# RTI-Dome-eth-ESP32.net
KiCad netlist of a schematic drawn in EAGLE
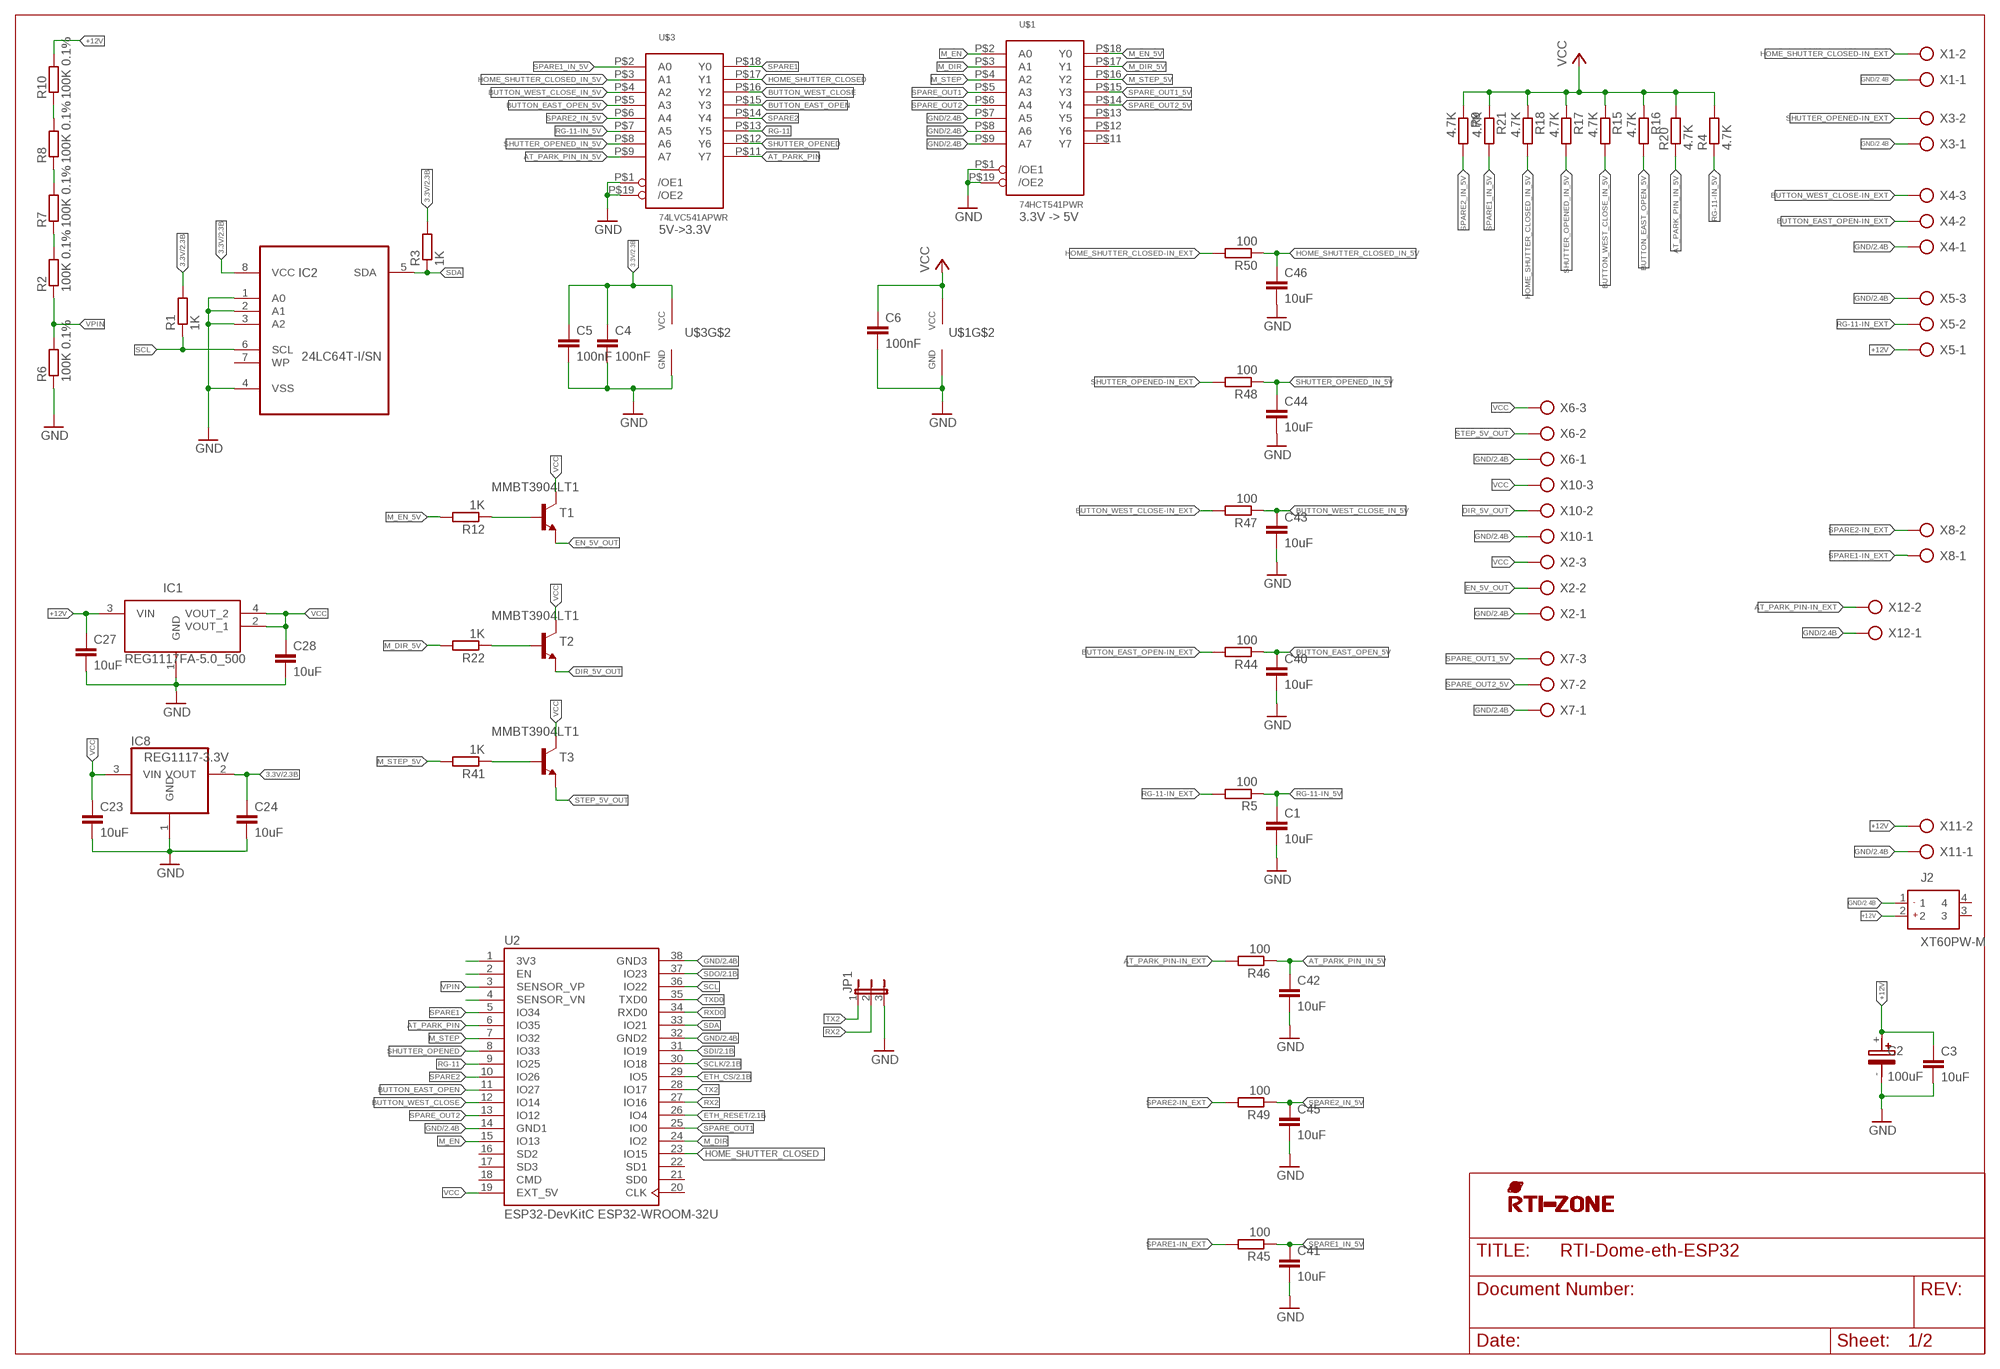
[diagram p0: schematic, sheet 1]
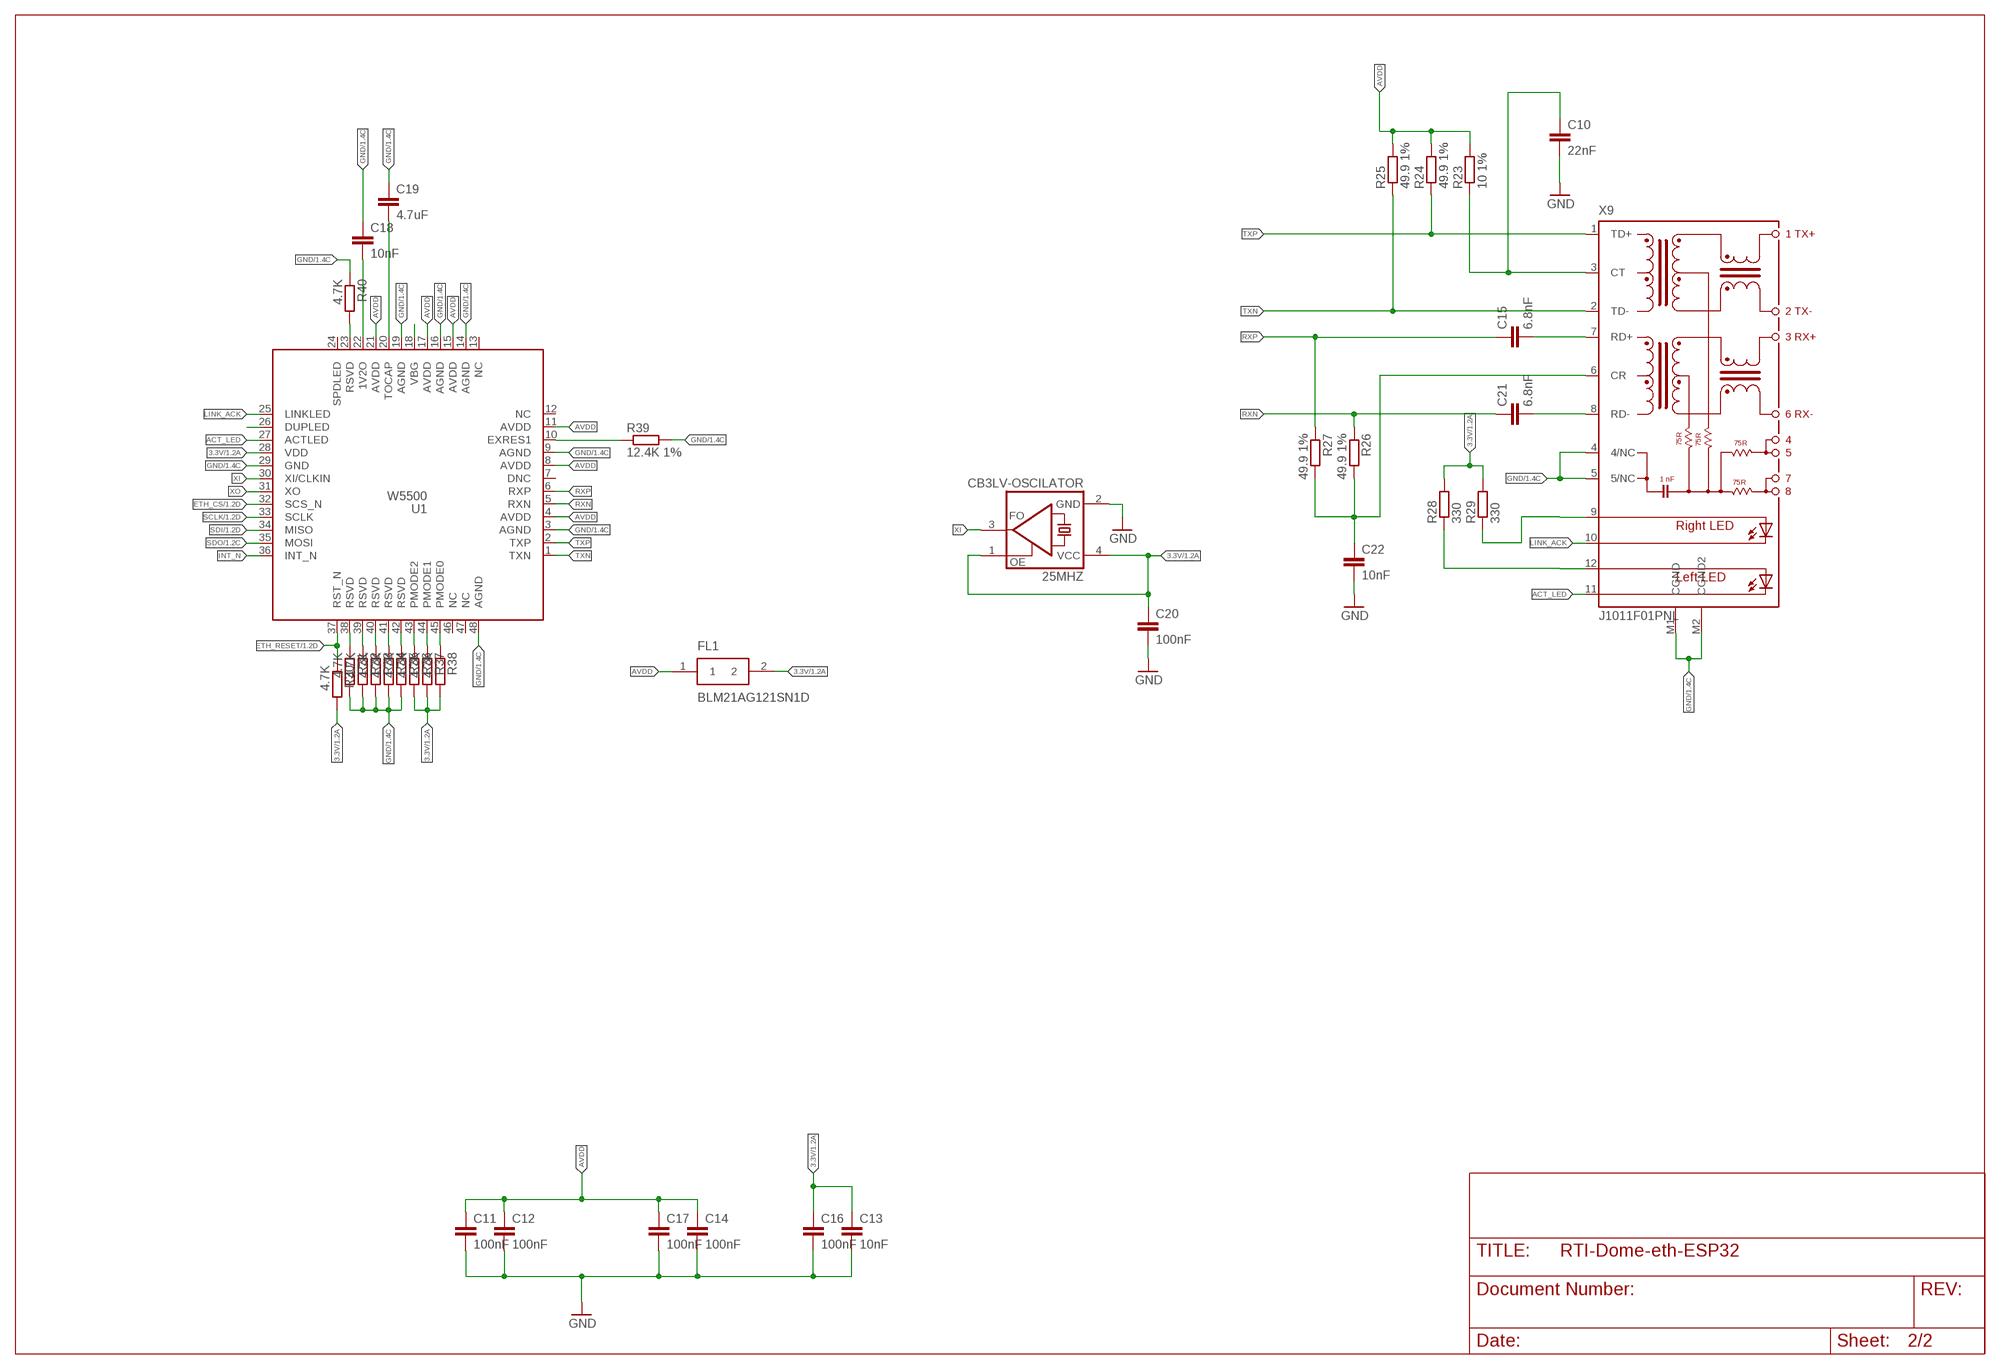
[diagram p1: schematic, sheet 2]

(export (version "E")
  (design (tool "Eeschema 10.0.6"))
  (components
    (comp (ref "C1")
      (value "10uF")
      (footprint "eagle-import:C0603")
      (fields (field (name "MPN") "CC0805KKX5R8BB106"))
      (libsource (lib "eagle-import") (part "C-EUC0603"))
    )
    (comp (ref "C2")
      (value "100uF")
      (footprint "eagle-import:UD-10X10_NICHICON")
      (fields (field (name "MPN") "MAL215099804E3"))
      (libsource (lib "eagle-import") (part "MAL215099804E3{dblquote}{dblquote}"))
    )
    (comp (ref "C3")
      (value "10uF")
      (footprint "eagle-import:C0603")
      (fields (field (name "MPN") "CC0805KKX5R8BB106"))
      (libsource (lib "eagle-import") (part "C-EUC0603"))
    )
    (comp (ref "C4")
      (value "100nF")
      (footprint "eagle-import:C0603")
      (fields (field (name "MPN") "0805YD104KAT2A"))
      (libsource (lib "eagle-import") (part "C-EUC0603"))
    )
    (comp (ref "C5")
      (value "100nF")
      (footprint "eagle-import:C0603")
      (fields (field (name "MPN") "0805YD104KAT2A"))
      (libsource (lib "eagle-import") (part "C-EUC0603"))
    )
    (comp (ref "C6")
      (value "100nF")
      (footprint "eagle-import:C0603")
      (fields (field (name "MPN") "0805YD104KAT2A"))
      (libsource (lib "eagle-import") (part "C-EUC0603"))
    )
    (comp (ref "C23")
      (value "10uF")
      (footprint "eagle-import:C0603")
      (fields (field (name "MPN") "CC0805KKX5R8BB106"))
      (libsource (lib "eagle-import") (part "C-EUC0603"))
    )
    (comp (ref "C24")
      (value "10uF")
      (footprint "eagle-import:C0603")
      (fields (field (name "MPN") "CC0805KKX5R8BB106"))
      (libsource (lib "eagle-import") (part "C-EUC0603"))
    )
    (comp (ref "C27")
      (value "10uF")
      (footprint "eagle-import:C0603")
      (fields (field (name "MPN") "CC0805KKX5R8BB106"))
      (libsource (lib "eagle-import") (part "C-EUC0603"))
    )
    (comp (ref "C28")
      (value "10uF")
      (footprint "eagle-import:C0603")
      (fields (field (name "MPN") "CC0805KKX5R8BB106"))
      (libsource (lib "eagle-import") (part "C-EUC0603"))
    )
    (comp (ref "C40")
      (value "10uF")
      (footprint "eagle-import:C0603")
      (fields (field (name "MPN") "CC0805KKX5R8BB106"))
      (libsource (lib "eagle-import") (part "C-EUC0603"))
    )
    (comp (ref "C41")
      (value "10uF")
      (footprint "eagle-import:C0603")
      (fields (field (name "MPN") "CC0805KKX5R8BB106"))
      (libsource (lib "eagle-import") (part "C-EUC0603"))
    )
    (comp (ref "C42")
      (value "10uF")
      (footprint "eagle-import:C0603")
      (fields (field (name "MPN") "CC0805KKX5R8BB106"))
      (libsource (lib "eagle-import") (part "C-EUC0603"))
    )
    (comp (ref "C43")
      (value "10uF")
      (footprint "eagle-import:C0603")
      (fields (field (name "MPN") "CC0805KKX5R8BB106"))
      (libsource (lib "eagle-import") (part "C-EUC0603"))
    )
    (comp (ref "C44")
      (value "10uF")
      (footprint "eagle-import:C0603")
      (fields (field (name "MPN") "CC0805KKX5R8BB106"))
      (libsource (lib "eagle-import") (part "C-EUC0603"))
    )
    (comp (ref "C45")
      (value "10uF")
      (footprint "eagle-import:C0603")
      (fields (field (name "MPN") "CC0805KKX5R8BB106"))
      (libsource (lib "eagle-import") (part "C-EUC0603"))
    )
    (comp (ref "C46")
      (value "10uF")
      (footprint "eagle-import:C0603")
      (fields (field (name "MPN") "CC0805KKX5R8BB106"))
      (libsource (lib "eagle-import") (part "C-EUC0603"))
    )
    (comp (ref "IC1")
      (value "REG1117FA-5.0_500")
      (footprint "eagle-import:REG1117FA50500")
      (fields
        (field (name "ARROW_PART_NUMBER") "REG1117FA-5.0/500")
        (field (name "MOUSER_PART_NUMBER") "595-REG1117FA50/500")
      )
      (libsource (lib "eagle-import") (part "REG1117FA-5.0_500"))
    )
    (comp (ref "IC2")
      (value "24LC64T-I/SN")
      (footprint "eagle-import:SOIC127P600X175-8N")
      (libsource (lib "eagle-import") (part "24LC64T-I/SN"))
    )
    (comp (ref "IC8")
      (value "REG1117-3.3V")
      (footprint "eagle-import:SOT223")
      (fields (field (name "MPN") "REG1117") (field (name "MPN_1") "REG1117-3.3/2K5"))
      (libsource (lib "eagle-import") (part "REG1117"))
    )
    (comp (ref "J2")
      (value "XT60PW-M")
      (footprint "eagle-import:XT60PWM")
      (libsource (lib "eagle-import") (part "XT60PW-M"))
    )
    (comp (ref "JP1")
      (value "JP2E")
      (footprint "eagle-import:JP2")
      (libsource (lib "eagle-import") (part "JP2E"))
    )
    (comp (ref "R1")
      (value "1K")
      (footprint "eagle-import:R0603")
      (fields (field (name "MPN") "RT0805FRE071KL"))
      (libsource (lib "eagle-import") (part "R-EU_R0603"))
    )
    (comp (ref "R2")
      (value "100K 0.1%")
      (footprint "eagle-import:R0603")
      (fields (field (name "MPN") "AT0805BRD07100KL"))
      (libsource (lib "eagle-import") (part "R-EU_R0603"))
    )
    (comp (ref "R3")
      (value "1K")
      (footprint "eagle-import:R0603")
      (fields (field (name "MPN") "RT0805FRE071KL"))
      (libsource (lib "eagle-import") (part "R-EU_R0603"))
    )
    (comp (ref "R4")
      (value "4.7K")
      (footprint "eagle-import:R0603")
      (fields (field (name "MPN") "RT0805FRE074K7L"))
      (libsource (lib "eagle-import") (part "R-EU_R0603"))
    )
    (comp (ref "R5")
      (value "100")
      (footprint "eagle-import:R0603")
      (fields (field (name "MPN") "RT0805FRD07100RL"))
      (libsource (lib "eagle-import") (part "R-EU_R0603"))
    )
    (comp (ref "R6")
      (value "100K 0.1%")
      (footprint "eagle-import:R0603")
      (fields (field (name "MPN") "AT0805BRD07100KL"))
      (libsource (lib "eagle-import") (part "R-EU_R0603"))
    )
    (comp (ref "R7")
      (value "100K 0.1%")
      (footprint "eagle-import:R0603")
      (fields (field (name "MPN") "AT0805BRD07100KL"))
      (libsource (lib "eagle-import") (part "R-EU_R0603"))
    )
    (comp (ref "R8")
      (value "100K 0.1%")
      (footprint "eagle-import:R0603")
      (fields (field (name "MPN") "AT0805BRD07100KL"))
      (libsource (lib "eagle-import") (part "R-EU_R0603"))
    )
    (comp (ref "R9")
      (value "4.7K")
      (footprint "eagle-import:R0603")
      (fields (field (name "MPN") "RT0805FRE074K7L"))
      (libsource (lib "eagle-import") (part "R-EU_R0603"))
    )
    (comp (ref "R10")
      (value "100K 0.1%")
      (footprint "eagle-import:R0603")
      (fields (field (name "MPN") "AT0805BRD07100KL"))
      (libsource (lib "eagle-import") (part "R-EU_R0603"))
    )
    (comp (ref "R12")
      (value "1K")
      (footprint "eagle-import:R0603")
      (fields (field (name "MPN") "RT0805FRE074K7L"))
      (libsource (lib "eagle-import") (part "R-EU_R0603"))
    )
    (comp (ref "R15")
      (value "4.7K")
      (footprint "eagle-import:R0603")
      (fields (field (name "MPN") "RT0805FRE074K7L"))
      (libsource (lib "eagle-import") (part "R-EU_R0603"))
    )
    (comp (ref "R16")
      (value "4.7K")
      (footprint "eagle-import:R0603")
      (fields (field (name "MPN") "RT0805FRE074K7L"))
      (libsource (lib "eagle-import") (part "R-EU_R0603"))
    )
    (comp (ref "R17")
      (value "4.7K")
      (footprint "eagle-import:R0603")
      (fields (field (name "MPN") "RT0805FRE074K7L"))
      (libsource (lib "eagle-import") (part "R-EU_R0603"))
    )
    (comp (ref "R18")
      (value "4.7K")
      (footprint "eagle-import:R0603")
      (fields (field (name "MPN") "RT0805FRE074K7L"))
      (libsource (lib "eagle-import") (part "R-EU_R0603"))
    )
    (comp (ref "R20")
      (value "4.7K")
      (footprint "eagle-import:R0603")
      (fields (field (name "MPN") "RT0805FRE074K7L"))
      (libsource (lib "eagle-import") (part "R-EU_R0603"))
    )
    (comp (ref "R21")
      (value "4.7K")
      (footprint "eagle-import:R0603")
      (fields (field (name "MPN") "RT0805FRE074K7L"))
      (libsource (lib "eagle-import") (part "R-EU_R0603"))
    )
    (comp (ref "R22")
      (value "1K")
      (footprint "eagle-import:R0603")
      (fields (field (name "MPN") "RT0805FRE074K7L"))
      (libsource (lib "eagle-import") (part "R-EU_R0603"))
    )
    (comp (ref "R41")
      (value "1K")
      (footprint "eagle-import:R0603")
      (fields (field (name "MPN") "RT0805FRE074K7L"))
      (libsource (lib "eagle-import") (part "R-EU_R0603"))
    )
    (comp (ref "R44")
      (value "100")
      (footprint "eagle-import:R0603")
      (fields (field (name "MPN") "RT0805FRD07100RL"))
      (libsource (lib "eagle-import") (part "R-EU_R0603"))
    )
    (comp (ref "R45")
      (value "100")
      (footprint "eagle-import:R0603")
      (fields (field (name "MPN") "RT0805FRD07100RL"))
      (libsource (lib "eagle-import") (part "R-EU_R0603"))
    )
    (comp (ref "R46")
      (value "100")
      (footprint "eagle-import:R0603")
      (fields (field (name "MPN") "RT0805FRD07100RL"))
      (libsource (lib "eagle-import") (part "R-EU_R0603"))
    )
    (comp (ref "R47")
      (value "100")
      (footprint "eagle-import:R0603")
      (fields (field (name "MPN") "RT0805FRD07100RL"))
      (libsource (lib "eagle-import") (part "R-EU_R0603"))
    )
    (comp (ref "R48")
      (value "100")
      (footprint "eagle-import:R0603")
      (fields (field (name "MPN") "RT0805FRD07100RL"))
      (libsource (lib "eagle-import") (part "R-EU_R0603"))
    )
    (comp (ref "R49")
      (value "100")
      (footprint "eagle-import:R0603")
      (fields (field (name "MPN") "RT0805FRD07100RL"))
      (libsource (lib "eagle-import") (part "R-EU_R0603"))
    )
    (comp (ref "R50")
      (value "100")
      (footprint "eagle-import:R0603")
      (fields (field (name "MPN") "RT0805FRD07100RL"))
      (libsource (lib "eagle-import") (part "R-EU_R0603"))
    )
    (comp (ref "T1")
      (value "MMBT3904LT1")
      (footprint "eagle-import:SOT23")
      (libsource (lib "eagle-import") (part "MMBT3904LT1"))
    )
    (comp (ref "T2")
      (value "MMBT3904LT1")
      (footprint "eagle-import:SOT23")
      (libsource (lib "eagle-import") (part "MMBT3904LT1"))
    )
    (comp (ref "T3")
      (value "MMBT3904LT1")
      (footprint "eagle-import:SOT23")
      (libsource (lib "eagle-import") (part "MMBT3904LT1"))
    )
    (comp (ref "U$1")
      (value "74HCT541PWR")
      (footprint "eagle-import:TSSOP20")
      (libsource (lib "eagle-import") (part "74541B"))
    )
    (comp (ref "U$3")
      (value "74LVC541APWR")
      (footprint "eagle-import:TSSOP20")
      (libsource (lib "eagle-import") (part "74541B"))
    )
    (comp (ref "U$4")
      (value "RTI-LOGO_BIG")
      (footprint "eagle-import:LOGO_BIG")
      (libsource (lib "eagle-import") (part "RTI-LOGO_BIG"))
    )
    (comp (ref "U2")
      (value "ESP32-DevKitC ESP32-WROOM-32U")
      (footprint "eagle-import:MODULE_ESP32-DEVKITC-32U")
      (libsource (lib "eagle-import") (part "ESP32-DEVKITC-32U"))
    )
    (comp (ref "X1")
      (value "AK500/2")
      (footprint "eagle-import:AK500_2")
      (fields (field (name "MPN") "691101710002"))
      (libsource (lib "eagle-import") (part "AK500/2"))
    )
    (comp (ref "X2")
      (value "AK500/3")
      (footprint "eagle-import:AK500_3")
      (libsource (lib "eagle-import") (part "AK500/3"))
    )
    (comp (ref "X3")
      (value "AK500/2")
      (footprint "eagle-import:AK500_2")
      (fields (field (name "MPN") "691101710002"))
      (libsource (lib "eagle-import") (part "AK500/2"))
    )
    (comp (ref "X4")
      (value "AK500/3")
      (footprint "eagle-import:AK500_3")
      (fields (field (name "MPN") "691101710003"))
      (libsource (lib "eagle-import") (part "AK500/3"))
    )
    (comp (ref "X5")
      (value "AK500/3")
      (footprint "eagle-import:AK500_3")
      (fields (field (name "MPN") "691101710003"))
      (libsource (lib "eagle-import") (part "AK500/3"))
    )
    (comp (ref "X6")
      (value "AK500/3")
      (footprint "eagle-import:AK500_3")
      (libsource (lib "eagle-import") (part "AK500/3"))
    )
    (comp (ref "X7")
      (value "AK500/3")
      (footprint "eagle-import:AK500_3")
      (libsource (lib "eagle-import") (part "AK500/3"))
    )
    (comp (ref "X8")
      (value "AK500/2")
      (footprint "eagle-import:AK500_2")
      (fields (field (name "MPN") "691101710002"))
      (libsource (lib "eagle-import") (part "AK500/2"))
    )
    (comp (ref "X10")
      (value "AK500/3")
      (footprint "eagle-import:AK500_3")
      (libsource (lib "eagle-import") (part "AK500/3"))
    )
    (comp (ref "X11")
      (value "AK500/2")
      (footprint "eagle-import:AK500_2")
      (fields (field (name "MPN") "691101710002"))
      (libsource (lib "eagle-import") (part "AK500/2"))
    )
    (comp (ref "X12")
      (value "AK500/2")
      (footprint "eagle-import:AK500_2")
      (fields (field (name "MPN") "691101710002"))
      (libsource (lib "eagle-import") (part "AK500/2"))
    )
    (comp (ref "25MHZ")
      (value "CB3LV-OSCILATOR")
      (footprint "eagle-import:SMD-7050_4P")
      (fields (field (name "MPN") "CB3LV-3I-25M0000"))
      (libsource (lib "eagle-import") (part "CB3LV-OSCILATOR"))
    )
    (comp (ref "C10")
      (value "22nF")
      (footprint "eagle-import:C0603")
      (fields (field (name "MPN") "CC0805JRX7R8BB223"))
      (libsource (lib "eagle-import") (part "C-EUC0603"))
    )
    (comp (ref "C11")
      (value "100nF")
      (footprint "eagle-import:C0603")
      (fields (field (name "MPN") "0805YD104KAT2A"))
      (libsource (lib "eagle-import") (part "C-EUC0603"))
    )
    (comp (ref "C12")
      (value "100nF")
      (footprint "eagle-import:C0603")
      (fields (field (name "MPN") "0805YD104KAT2A"))
      (libsource (lib "eagle-import") (part "C-EUC0603"))
    )
    (comp (ref "C13")
      (value "10nF")
      (footprint "eagle-import:C0603")
      (fields (field (name "MPN") " CC0805KRX7R9BB103"))
      (libsource (lib "eagle-import") (part "C-EUC0603"))
    )
    (comp (ref "C14")
      (value "100nF")
      (footprint "eagle-import:C0603")
      (fields (field (name "MPN") "0805YD104KAT2A"))
      (libsource (lib "eagle-import") (part "C-EUC0603"))
    )
    (comp (ref "C15")
      (value "6.8nF")
      (footprint "eagle-import:C0603")
      (fields (field (name "MPN") "C0805C682F4HACTU"))
      (libsource (lib "eagle-import") (part "C-EUC0603"))
    )
    (comp (ref "C16")
      (value "100nF")
      (footprint "eagle-import:C0603")
      (fields (field (name "MPN") "0805YD104KAT2A"))
      (libsource (lib "eagle-import") (part "C-EUC0603"))
    )
    (comp (ref "C17")
      (value "100nF")
      (footprint "eagle-import:C0603")
      (fields (field (name "MPN") "0805YD104KAT2A"))
      (libsource (lib "eagle-import") (part "C-EUC0603"))
    )
    (comp (ref "C18")
      (value "10nF")
      (footprint "eagle-import:C0603")
      (fields (field (name "MPN") " CC0805KRX7R9BB103"))
      (libsource (lib "eagle-import") (part "C-EUC0603"))
    )
    (comp (ref "C19")
      (value "4.7uF")
      (footprint "eagle-import:C0603")
      (fields (field (name "MPN") "C0805C475J3RACTU"))
      (libsource (lib "eagle-import") (part "C-EUC0603"))
    )
    (comp (ref "C20")
      (value "100nF")
      (footprint "eagle-import:C0603")
      (fields (field (name "MPN") "0805YD104KAT2A"))
      (libsource (lib "eagle-import") (part "C-EUC0603"))
    )
    (comp (ref "C21")
      (value "6.8nF")
      (footprint "eagle-import:C0603")
      (fields (field (name "MPN") "C0805C682F4HACTU"))
      (libsource (lib "eagle-import") (part "C-EUC0603"))
    )
    (comp (ref "C22")
      (value "10nF")
      (footprint "eagle-import:C0603")
      (fields (field (name "MPN") " CC0805KRX7R9BB103"))
      (libsource (lib "eagle-import") (part "C-EUC0603"))
    )
    (comp (ref "FL1")
      (value "BLM21AG121SN1D")
      (footprint "eagle-import:L0805")
      (libsource (lib "eagle-import") (part "BLM21AG121SN1D"))
    )
    (comp (ref "R23")
      (value "10 1%")
      (footprint "eagle-import:R0603")
      (fields (field (name "MPN") "RT0805FRE1310RL"))
      (libsource (lib "eagle-import") (part "R-EU_R0603"))
    )
    (comp (ref "R24")
      (value "49.9 1%")
      (footprint "eagle-import:R0603")
      (fields (field (name "MPN") "RC0805FR-0749R9L"))
      (libsource (lib "eagle-import") (part "R-EU_R0603"))
    )
    (comp (ref "R25")
      (value "49.9 1%")
      (footprint "eagle-import:R0603")
      (fields (field (name "MPN") "RC0805FR-0749R9L"))
      (libsource (lib "eagle-import") (part "R-EU_R0603"))
    )
    (comp (ref "R26")
      (value "49.9 1%")
      (footprint "eagle-import:R0603")
      (fields (field (name "MPN") "RC0805FR-0749R9L"))
      (libsource (lib "eagle-import") (part "R-EU_R0603"))
    )
    (comp (ref "R27")
      (value "49.9 1%")
      (footprint "eagle-import:R0603")
      (fields (field (name "MPN") "RC0805FR-0749R9L"))
      (libsource (lib "eagle-import") (part "R-EU_R0603"))
    )
    (comp (ref "R28")
      (value "330")
      (footprint "eagle-import:R0603")
      (fields (field (name "MPN") " RC0805JR-07330RL"))
      (libsource (lib "eagle-import") (part "R-EU_R0603"))
    )
    (comp (ref "R29")
      (value "330")
      (footprint "eagle-import:R0603")
      (fields (field (name "MPN") " RC0805JR-07330RL"))
      (libsource (lib "eagle-import") (part "R-EU_R0603"))
    )
    (comp (ref "R30")
      (value "4.7K")
      (footprint "eagle-import:R0603")
      (fields (field (name "MPN") "RT0805FRE074K7L"))
      (libsource (lib "eagle-import") (part "R-EU_R0603"))
    )
    (comp (ref "R31")
      (value "4.7K")
      (footprint "eagle-import:R0603")
      (fields (field (name "MPN") "RT0805FRE074K7L"))
      (libsource (lib "eagle-import") (part "R-EU_R0603"))
    )
    (comp (ref "R32")
      (value "4.7K")
      (footprint "eagle-import:R0603")
      (fields (field (name "MPN") "RT0805FRE074K7L"))
      (libsource (lib "eagle-import") (part "R-EU_R0603"))
    )
    (comp (ref "R33")
      (value "4.7K")
      (footprint "eagle-import:R0603")
      (fields (field (name "MPN") "RT0805FRE074K7L"))
      (libsource (lib "eagle-import") (part "R-EU_R0603"))
    )
    (comp (ref "R34")
      (value "4.7K")
      (footprint "eagle-import:R0603")
      (fields (field (name "MPN") "RT0805FRE074K7L"))
      (libsource (lib "eagle-import") (part "R-EU_R0603"))
    )
    (comp (ref "R35")
      (value "4.7K")
      (footprint "eagle-import:R0603")
      (fields (field (name "MPN") "RT0805FRE074K7L"))
      (libsource (lib "eagle-import") (part "R-EU_R0603"))
    )
    (comp (ref "R36")
      (value "4.7K")
      (footprint "eagle-import:R0603")
      (fields (field (name "MPN") "RT0805FRE074K7L"))
      (libsource (lib "eagle-import") (part "R-EU_R0603"))
    )
    (comp (ref "R37")
      (value "4.7K")
      (footprint "eagle-import:R0603")
      (fields (field (name "MPN") "RT0805FRE074K7L"))
      (libsource (lib "eagle-import") (part "R-EU_R0603"))
    )
    (comp (ref "R38")
      (value "4.7K")
      (footprint "eagle-import:R0603")
      (fields (field (name "MPN") "RT0805FRE074K7L"))
      (libsource (lib "eagle-import") (part "R-EU_R0603"))
    )
    (comp (ref "R39")
      (value "12.4K 1%")
      (footprint "eagle-import:R0603")
      (fields (field (name "MPN") "RC0805FR-0712K4L"))
      (libsource (lib "eagle-import") (part "R-EU_R0603"))
    )
    (comp (ref "R40")
      (value "4.7K")
      (footprint "eagle-import:R0603")
      (fields (field (name "MPN") "RT0805FRE074K7L"))
      (libsource (lib "eagle-import") (part "R-EU_R0603"))
    )
    (comp (ref "U1")
      (value "W5500")
      (footprint "eagle-import:LQFP48")
      (libsource (lib "eagle-import") (part "W5500"))
    )
    (comp (ref "X9")
      (value "J1011F01PNL")
      (footprint "eagle-import:J1011F01PNL")
      (libsource (lib "eagle-import") (part "J1011F01PNL"))
    )
  )
  (nets
    (net (code "1") (name "+12V") (class "Default")
      (node (ref "C2") (pin "+") (pinfunction "+_+") (pintype "bidirectional"))
      (node (ref "C27") (pin "1") (pinfunction "1_1") (pintype "passive"))
      (node (ref "C3") (pin "1") (pinfunction "1_1") (pintype "passive"))
      (node (ref "IC1") (pin "3") (pinfunction "VIN_3") (pintype "bidirectional"))
      (node (ref "J2") (pin "2") (pinfunction "2_2") (pintype "bidirectional"))
      (node (ref "R10") (pin "2") (pinfunction "2_2") (pintype "passive"))
      (node (ref "X11") (pin "2") (pinfunction "KL_2") (pintype "passive"))
      (node (ref "X5") (pin "1") (pinfunction "KL_1") (pintype "passive"))
    )
    (net (code "2") (name "3.3V") (class "Default")
      (node (ref "25MHZ") (pin "1") (pinfunction "OE_1") (pintype "input"))
      (node (ref "25MHZ") (pin "4") (pinfunction "VDD_4") (pintype "power_in"))
      (node (ref "C13") (pin "1") (pinfunction "1_1") (pintype "passive"))
      (node (ref "C16") (pin "1") (pinfunction "1_1") (pintype "passive"))
      (node (ref "C20") (pin "1") (pinfunction "1_1") (pintype "passive"))
      (node (ref "C24") (pin "1") (pinfunction "1_1") (pintype "passive"))
      (node (ref "C4") (pin "1") (pinfunction "1_1") (pintype "passive"))
      (node (ref "C5") (pin "1") (pinfunction "1_1") (pintype "passive"))
      (node (ref "FL1") (pin "2") (pinfunction "2_2") (pintype "bidirectional"))
      (node (ref "IC2") (pin "8") (pinfunction "VCC_8") (pintype "power_in"))
      (node (ref "IC8") (pin "2") (pinfunction "VOUT_2") (pintype "output"))
      (node (ref "R1") (pin "2") (pinfunction "2_2") (pintype "passive"))
      (node (ref "R28") (pin "2") (pinfunction "2_2") (pintype "passive"))
      (node (ref "R29") (pin "2") (pinfunction "2_2") (pintype "passive"))
      (node (ref "R3") (pin "2") (pinfunction "2_2") (pintype "passive"))
      (node (ref "R30") (pin "2") (pinfunction "2_2") (pintype "passive"))
      (node (ref "R36") (pin "2") (pinfunction "2_2") (pintype "passive"))
      (node (ref "R37") (pin "2") (pinfunction "2_2") (pintype "passive"))
      (node (ref "R38") (pin "2") (pinfunction "2_2") (pintype "passive"))
      (node (ref "U$3") (pin "P$20") (pinfunction "VCC_P$20") (pintype "power_in"))
      (node (ref "U1") (pin "28") (pinfunction "VDD_28") (pintype "passive"))
    )
    (net (code "3") (name "ACT_LED") (class "Default")
      (node (ref "U1") (pin "27") (pinfunction "ACTLED_27") (pintype "passive"))
      (node (ref "X9") (pin "11") (pinfunction "C-L_11") (pintype "passive"))
    )
    (net (code "4") (name "AT_PARK_PIN") (class "Default")
      (node (ref "U$3") (pin "P$11") (pinfunction "Y7_P$11") (pintype "output"))
      (node (ref "U2") (pin "6") (pinfunction "IO35_6") (pintype "bidirectional"))
    )
    (net (code "5") (name "AT_PARK_PIN-IN_EXT") (class "Default")
      (node (ref "R46") (pin "2") (pinfunction "2_2") (pintype "passive"))
      (node (ref "X12") (pin "2") (pinfunction "KL_2") (pintype "passive"))
    )
    (net (code "6") (name "AT_PARK_PIN_IN_5V") (class "Default")
      (node (ref "C42") (pin "1") (pinfunction "1_1") (pintype "passive"))
      (node (ref "R20") (pin "1") (pinfunction "1_1") (pintype "passive"))
      (node (ref "R46") (pin "1") (pinfunction "1_1") (pintype "passive"))
      (node (ref "U$3") (pin "P$9") (pinfunction "A7_P$9") (pintype "input"))
    )
    (net (code "7") (name "AVDD") (class "Default")
      (node (ref "C11") (pin "1") (pinfunction "1_1") (pintype "passive"))
      (node (ref "C12") (pin "1") (pinfunction "1_1") (pintype "passive"))
      (node (ref "C14") (pin "1") (pinfunction "1_1") (pintype "passive"))
      (node (ref "C17") (pin "1") (pinfunction "1_1") (pintype "passive"))
      (node (ref "FL1") (pin "1") (pinfunction "1_1") (pintype "bidirectional"))
      (node (ref "R23") (pin "2") (pinfunction "2_2") (pintype "passive"))
      (node (ref "R24") (pin "2") (pinfunction "2_2") (pintype "passive"))
      (node (ref "R25") (pin "2") (pinfunction "2_2") (pintype "passive"))
      (node (ref "U1") (pin "11") (pinfunction "AVDD_11") (pintype "passive"))
      (node (ref "U1") (pin "15") (pinfunction "AVDD_15") (pintype "passive"))
      (node (ref "U1") (pin "17") (pinfunction "AVDD_17") (pintype "passive"))
      (node (ref "U1") (pin "21") (pinfunction "AVDD_21") (pintype "passive"))
      (node (ref "U1") (pin "4") (pinfunction "AVDD_4") (pintype "passive"))
      (node (ref "U1") (pin "8") (pinfunction "AVDD_8") (pintype "passive"))
    )
    (net (code "8") (name "BUTTON_EAST_OPEN") (class "Default")
      (node (ref "U$3") (pin "P$15") (pinfunction "Y3_P$15") (pintype "output"))
      (node (ref "U2") (pin "11") (pinfunction "IO27_11") (pintype "bidirectional"))
    )
    (net (code "9") (name "BUTTON_EAST_OPEN-IN_EXT") (class "Default")
      (node (ref "R44") (pin "2") (pinfunction "2_2") (pintype "passive"))
      (node (ref "X4") (pin "2") (pinfunction "KL_2") (pintype "passive"))
    )
    (net (code "10") (name "BUTTON_EAST_OPEN_5V") (class "Default")
      (node (ref "C40") (pin "1") (pinfunction "1_1") (pintype "passive"))
      (node (ref "R16") (pin "2") (pinfunction "2_2") (pintype "passive"))
      (node (ref "R44") (pin "1") (pinfunction "1_1") (pintype "passive"))
      (node (ref "U$3") (pin "P$5") (pinfunction "A3_P$5") (pintype "input"))
    )
    (net (code "11") (name "BUTTON_WEST_CLOSE") (class "Default")
      (node (ref "U$3") (pin "P$16") (pinfunction "Y2_P$16") (pintype "output"))
      (node (ref "U2") (pin "12") (pinfunction "IO14_12") (pintype "bidirectional"))
    )
    (net (code "12") (name "BUTTON_WEST_CLOSE-IN_EXT") (class "Default")
      (node (ref "R47") (pin "2") (pinfunction "2_2") (pintype "passive"))
      (node (ref "X4") (pin "3") (pinfunction "KL_3") (pintype "passive"))
    )
    (net (code "13") (name "BUTTON_WEST_CLOSE_IN_5V") (class "Default")
      (node (ref "C43") (pin "1") (pinfunction "1_1") (pintype "passive"))
      (node (ref "R15") (pin "2") (pinfunction "2_2") (pintype "passive"))
      (node (ref "R47") (pin "1") (pinfunction "1_1") (pintype "passive"))
      (node (ref "U$3") (pin "P$4") (pinfunction "A2_P$4") (pintype "input"))
    )
    (net (code "14") (name "DIR_5V_OUT") (class "Default")
      (node (ref "T2") (pin "2") (pinfunction "E_2") (pintype "passive"))
      (node (ref "X10") (pin "2") (pinfunction "KL_2") (pintype "passive"))
    )
    (net (code "15") (name "EN_5V_OUT") (class "Default")
      (node (ref "T1") (pin "2") (pinfunction "E_2") (pintype "passive"))
      (node (ref "X2") (pin "2") (pinfunction "KL_2") (pintype "passive"))
    )
    (net (code "16") (name "ETH_CS") (class "Default")
      (node (ref "U1") (pin "32") (pinfunction "SCS_N_32") (pintype "passive"))
      (node (ref "U2") (pin "29") (pinfunction "IO5_29") (pintype "bidirectional"))
    )
    (net (code "17") (name "ETH_RESET") (class "Default")
      (node (ref "R30") (pin "1") (pinfunction "1_1") (pintype "passive"))
      (node (ref "U1") (pin "37") (pinfunction "RST_N_37") (pintype "passive"))
      (node (ref "U2") (pin "26") (pinfunction "IO4_26") (pintype "bidirectional"))
    )
    (net (code "18") (name "GND") (class "Default")
      (node (ref "25MHZ") (pin "2") (pinfunction "GND_2") (pintype "power_in"))
      (node (ref "C1") (pin "2") (pinfunction "2_2") (pintype "passive"))
      (node (ref "C10") (pin "2") (pinfunction "2_2") (pintype "passive"))
      (node (ref "C11") (pin "2") (pinfunction "2_2") (pintype "passive"))
      (node (ref "C12") (pin "2") (pinfunction "2_2") (pintype "passive"))
      (node (ref "C13") (pin "2") (pinfunction "2_2") (pintype "passive"))
      (node (ref "C14") (pin "2") (pinfunction "2_2") (pintype "passive"))
      (node (ref "C16") (pin "2") (pinfunction "2_2") (pintype "passive"))
      (node (ref "C17") (pin "2") (pinfunction "2_2") (pintype "passive"))
      (node (ref "C18") (pin "1") (pinfunction "1_1") (pintype "passive"))
      (node (ref "C19") (pin "1") (pinfunction "1_1") (pintype "passive"))
      (node (ref "C2") (pin "-") (pinfunction "-_-") (pintype "bidirectional"))
      (node (ref "C20") (pin "2") (pinfunction "2_2") (pintype "passive"))
      (node (ref "C22") (pin "2") (pinfunction "2_2") (pintype "passive"))
      (node (ref "C23") (pin "2") (pinfunction "2_2") (pintype "passive"))
      (node (ref "C24") (pin "2") (pinfunction "2_2") (pintype "passive"))
      (node (ref "C27") (pin "2") (pinfunction "2_2") (pintype "passive"))
      (node (ref "C28") (pin "2") (pinfunction "2_2") (pintype "passive"))
      (node (ref "C3") (pin "2") (pinfunction "2_2") (pintype "passive"))
      (node (ref "C4") (pin "2") (pinfunction "2_2") (pintype "passive"))
      (node (ref "C40") (pin "2") (pinfunction "2_2") (pintype "passive"))
      (node (ref "C41") (pin "2") (pinfunction "2_2") (pintype "passive"))
      (node (ref "C42") (pin "2") (pinfunction "2_2") (pintype "passive"))
      (node (ref "C43") (pin "2") (pinfunction "2_2") (pintype "passive"))
      (node (ref "C44") (pin "2") (pinfunction "2_2") (pintype "passive"))
      (node (ref "C45") (pin "2") (pinfunction "2_2") (pintype "passive"))
      (node (ref "C46") (pin "2") (pinfunction "2_2") (pintype "passive"))
      (node (ref "C5") (pin "2") (pinfunction "2_2") (pintype "passive"))
      (node (ref "C6") (pin "2") (pinfunction "2_2") (pintype "passive"))
      (node (ref "IC1") (pin "1") (pinfunction "GND_1") (pintype "bidirectional"))
      (node (ref "IC2") (pin "1") (pinfunction "A0_1") (pintype "input"))
      (node (ref "IC2") (pin "2") (pinfunction "A1_2") (pintype "input"))
      (node (ref "IC2") (pin "3") (pinfunction "A2_3") (pintype "input"))
      (node (ref "IC2") (pin "4") (pinfunction "VSS_4") (pintype "passive"))
      (node (ref "IC8") (pin "1") (pinfunction "GND_1") (pintype "power_in"))
      (node (ref "J2") (pin "1") (pinfunction "1_1") (pintype "bidirectional"))
      (node (ref "JP1") (pin "3") (pinfunction "3_3") (pintype "passive"))
      (node (ref "R31") (pin "2") (pinfunction "2_2") (pintype "passive"))
      (node (ref "R32") (pin "2") (pinfunction "2_2") (pintype "passive"))
      (node (ref "R33") (pin "2") (pinfunction "2_2") (pintype "passive"))
      (node (ref "R34") (pin "2") (pinfunction "2_2") (pintype "passive"))
      (node (ref "R35") (pin "2") (pinfunction "2_2") (pintype "passive"))
      (node (ref "R39") (pin "2") (pinfunction "2_2") (pintype "passive"))
      (node (ref "R40") (pin "1") (pinfunction "1_1") (pintype "passive"))
      (node (ref "R6") (pin "1") (pinfunction "1_1") (pintype "passive"))
      (node (ref "U$1") (pin "P$1") (pinfunction "/OE1_P$1") (pintype "input"))
      (node (ref "U$1") (pin "P$10") (pinfunction "GND_P$10") (pintype "power_in"))
      (node (ref "U$1") (pin "P$19") (pinfunction "/OE2_P$19") (pintype "input"))
      (node (ref "U$1") (pin "P$7") (pinfunction "A5_P$7") (pintype "input"))
      (node (ref "U$1") (pin "P$8") (pinfunction "A6_P$8") (pintype "input"))
      (node (ref "U$1") (pin "P$9") (pinfunction "A7_P$9") (pintype "input"))
      (node (ref "U$3") (pin "P$1") (pinfunction "/OE1_P$1") (pintype "input"))
      (node (ref "U$3") (pin "P$10") (pinfunction "GND_P$10") (pintype "power_in"))
      (node (ref "U$3") (pin "P$19") (pinfunction "/OE2_P$19") (pintype "input"))
      (node (ref "U1") (pin "14") (pinfunction "AGND_14") (pintype "passive"))
      (node (ref "U1") (pin "16") (pinfunction "AGND_16") (pintype "passive"))
      (node (ref "U1") (pin "19") (pinfunction "AGND_19") (pintype "passive"))
      (node (ref "U1") (pin "29") (pinfunction "GND_29") (pintype "passive"))
      (node (ref "U1") (pin "3") (pinfunction "AGND_3") (pintype "passive"))
      (node (ref "U1") (pin "48") (pinfunction "AGND_48") (pintype "passive"))
      (node (ref "U1") (pin "9") (pinfunction "AGND_9") (pintype "passive"))
      (node (ref "U2") (pin "14") (pinfunction "GND1_14") (pintype "power_in"))
      (node (ref "U2") (pin "32") (pinfunction "GND2_32") (pintype "power_in"))
      (node (ref "U2") (pin "38") (pinfunction "GND3_38") (pintype "power_in"))
      (node (ref "X1") (pin "1") (pinfunction "KL_1") (pintype "passive"))
      (node (ref "X10") (pin "1") (pinfunction "KL_1") (pintype "passive"))
      (node (ref "X11") (pin "1") (pinfunction "KL_1") (pintype "passive"))
      (node (ref "X12") (pin "1") (pinfunction "KL_1") (pintype "passive"))
      (node (ref "X2") (pin "1") (pinfunction "KL_1") (pintype "passive"))
      (node (ref "X3") (pin "1") (pinfunction "KL_1") (pintype "passive"))
      (node (ref "X4") (pin "1") (pinfunction "KL_1") (pintype "passive"))
      (node (ref "X5") (pin "3") (pinfunction "KL_3") (pintype "passive"))
      (node (ref "X6") (pin "1") (pinfunction "KL_1") (pintype "passive"))
      (node (ref "X7") (pin "1") (pinfunction "KL_1") (pintype "passive"))
      (node (ref "X9") (pin "4") (pinfunction "4/NC_4") (pintype "input"))
      (node (ref "X9") (pin "5") (pinfunction "5/NC_5") (pintype "input"))
      (node (ref "X9") (pin "M1") (pinfunction "CGND_M1") (pintype "bidirectional"))
      (node (ref "X9") (pin "M2") (pinfunction "CGND2_M2") (pintype "bidirectional"))
    )
    (net (code "19") (name "HOME_SHUTTER_CLOSED") (class "Default")
      (node (ref "U$3") (pin "P$17") (pinfunction "Y1_P$17") (pintype "output"))
      (node (ref "U2") (pin "23") (pinfunction "IO15_23") (pintype "bidirectional"))
    )
    (net (code "20") (name "HOME_SHUTTER_CLOSED-IN_EXT") (class "Default")
      (node (ref "R50") (pin "2") (pinfunction "2_2") (pintype "passive"))
      (node (ref "X1") (pin "2") (pinfunction "KL_2") (pintype "passive"))
    )
    (net (code "21") (name "HOME_SHUTTER_CLOSED_IN_5V") (class "Default")
      (node (ref "C46") (pin "1") (pinfunction "1_1") (pintype "passive"))
      (node (ref "R18") (pin "2") (pinfunction "2_2") (pintype "passive"))
      (node (ref "R50") (pin "1") (pinfunction "1_1") (pintype "passive"))
      (node (ref "U$3") (pin "P$3") (pinfunction "A1_P$3") (pintype "input"))
    )
    (net (code "22") (name "INT_N") (class "Default")
      (node (ref "U1") (pin "36") (pinfunction "INT_N_36") (pintype "passive"))
    )
    (net (code "23") (name "LINK_ACK") (class "Default")
      (node (ref "U1") (pin "25") (pinfunction "LINKLED_25") (pintype "passive"))
      (node (ref "X9") (pin "10") (pinfunction "C-R_10") (pintype "passive"))
    )
    (net (code "24") (name "M_DIR") (class "Default")
      (node (ref "U$1") (pin "P$3") (pinfunction "A1_P$3") (pintype "input"))
      (node (ref "U2") (pin "24") (pinfunction "IO2_24") (pintype "bidirectional"))
    )
    (net (code "25") (name "M_DIR_5V") (class "Default")
      (node (ref "R22") (pin "2") (pinfunction "2_2") (pintype "passive"))
      (node (ref "U$1") (pin "P$17") (pinfunction "Y1_P$17") (pintype "output"))
    )
    (net (code "26") (name "M_EN") (class "Default")
      (node (ref "U$1") (pin "P$2") (pinfunction "A0_P$2") (pintype "input"))
      (node (ref "U2") (pin "15") (pinfunction "IO13_15") (pintype "bidirectional"))
    )
    (net (code "27") (name "M_EN_5V") (class "Default")
      (node (ref "R12") (pin "2") (pinfunction "2_2") (pintype "passive"))
      (node (ref "U$1") (pin "P$18") (pinfunction "Y0_P$18") (pintype "output"))
    )
    (net (code "28") (name "M_STEP") (class "Default")
      (node (ref "U$1") (pin "P$4") (pinfunction "A2_P$4") (pintype "input"))
      (node (ref "U2") (pin "7") (pinfunction "IO32_7") (pintype "bidirectional"))
    )
    (net (code "29") (name "M_STEP_5V") (class "Default")
      (node (ref "R41") (pin "2") (pinfunction "2_2") (pintype "passive"))
      (node (ref "U$1") (pin "P$16") (pinfunction "Y2_P$16") (pintype "output"))
    )
    (net (code "30") (name "Net-(R2-Pad2)") (class "Default")
      (node (ref "R2") (pin "2") (pinfunction "2_2") (pintype "passive"))
      (node (ref "R7") (pin "1") (pinfunction "1_1") (pintype "passive"))
    )
    (net (code "31") (name "Net-(R7-Pad2)") (class "Default")
      (node (ref "R7") (pin "2") (pinfunction "2_2") (pintype "passive"))
      (node (ref "R8") (pin "1") (pinfunction "1_1") (pintype "passive"))
    )
    (net (code "32") (name "Net-(R10-Pad1)") (class "Default")
      (node (ref "R10") (pin "1") (pinfunction "1_1") (pintype "passive"))
      (node (ref "R8") (pin "2") (pinfunction "2_2") (pintype "passive"))
    )
    (net (code "33") (name "Net-(R31-Pad1)") (class "Default")
      (node (ref "R31") (pin "1") (pinfunction "1_1") (pintype "passive"))
      (node (ref "U1") (pin "38") (pinfunction "RSVD_38") (pintype "passive"))
    )
    (net (code "34") (name "Net-(R32-Pad1)") (class "Default")
      (node (ref "R32") (pin "1") (pinfunction "1_1") (pintype "passive"))
      (node (ref "U1") (pin "39") (pinfunction "RSVD_39") (pintype "passive"))
    )
    (net (code "35") (name "Net-(R33-Pad1)") (class "Default")
      (node (ref "R33") (pin "1") (pinfunction "1_1") (pintype "passive"))
      (node (ref "U1") (pin "40") (pinfunction "RSVD_40") (pintype "passive"))
    )
    (net (code "36") (name "Net-(R34-Pad1)") (class "Default")
      (node (ref "R34") (pin "1") (pinfunction "1_1") (pintype "passive"))
      (node (ref "U1") (pin "41") (pinfunction "RSVD_41") (pintype "passive"))
    )
    (net (code "37") (name "Net-(R35-Pad1)") (class "Default")
      (node (ref "R35") (pin "1") (pinfunction "1_1") (pintype "passive"))
      (node (ref "U1") (pin "42") (pinfunction "RSVD_42") (pintype "passive"))
    )
    (net (code "38") (name "Net-(R40-Pad2)") (class "Default")
      (node (ref "R40") (pin "2") (pinfunction "2_2") (pintype "passive"))
      (node (ref "U1") (pin "23") (pinfunction "RSVD_23") (pintype "passive"))
    )
    (net (code "39") (name "Net-(T1-B)") (class "Default")
      (node (ref "R12") (pin "1") (pinfunction "1_1") (pintype "passive"))
      (node (ref "T1") (pin "1") (pinfunction "B_1") (pintype "passive"))
    )
    (net (code "40") (name "Net-(T2-B)") (class "Default")
      (node (ref "R22") (pin "1") (pinfunction "1_1") (pintype "passive"))
      (node (ref "T2") (pin "1") (pinfunction "B_1") (pintype "passive"))
    )
    (net (code "41") (name "Net-(T3-B)") (class "Default")
      (node (ref "R41") (pin "1") (pinfunction "1_1") (pintype "passive"))
      (node (ref "T3") (pin "1") (pinfunction "B_1") (pintype "passive"))
    )
    (net (code "42") (name "Net-(U1-1V2O)") (class "Default")
      (node (ref "C18") (pin "2") (pinfunction "2_2") (pintype "passive"))
      (node (ref "U1") (pin "22") (pinfunction "1V2O_22") (pintype "passive"))
    )
    (net (code "43") (name "Net-(U1-EXRES1)") (class "Default")
      (node (ref "R39") (pin "1") (pinfunction "1_1") (pintype "passive"))
      (node (ref "U1") (pin "10") (pinfunction "EXRES1_10") (pintype "passive"))
    )
    (net (code "44") (name "Net-(U1-PMODE0)") (class "Default")
      (node (ref "R38") (pin "1") (pinfunction "1_1") (pintype "passive"))
      (node (ref "U1") (pin "45") (pinfunction "PMODE0_45") (pintype "passive"))
    )
    (net (code "45") (name "Net-(U1-PMODE1)") (class "Default")
      (node (ref "R37") (pin "1") (pinfunction "1_1") (pintype "passive"))
      (node (ref "U1") (pin "44") (pinfunction "PMODE1_44") (pintype "passive"))
    )
    (net (code "46") (name "Net-(U1-PMODE2)") (class "Default")
      (node (ref "R36") (pin "1") (pinfunction "1_1") (pintype "passive"))
      (node (ref "U1") (pin "43") (pinfunction "PMODE2_43") (pintype "passive"))
    )
    (net (code "47") (name "Net-(U1-TOCAP)") (class "Default")
      (node (ref "C19") (pin "2") (pinfunction "2_2") (pintype "passive"))
      (node (ref "U1") (pin "20") (pinfunction "TOCAP_20") (pintype "passive"))
    )
    (net (code "48") (name "Net-(X9-A-R)") (class "Default")
      (node (ref "R29") (pin "1") (pinfunction "1_1") (pintype "passive"))
      (node (ref "X9") (pin "9") (pinfunction "A-R_9") (pintype "passive"))
    )
    (net (code "49") (name "Net-(X9-AL)") (class "Default")
      (node (ref "R28") (pin "1") (pinfunction "1_1") (pintype "passive"))
      (node (ref "X9") (pin "12") (pinfunction "AL_12") (pintype "passive"))
    )
    (net (code "50") (name "Net-(X9-CR)") (class "Default")
      (node (ref "C22") (pin "1") (pinfunction "1_1") (pintype "passive"))
      (node (ref "R26") (pin "2") (pinfunction "2_2") (pintype "passive"))
      (node (ref "R27") (pin "2") (pinfunction "2_2") (pintype "passive"))
      (node (ref "X9") (pin "6") (pinfunction "CR_6") (pintype "input"))
    )
    (net (code "51") (name "Net-(X9-CT)") (class "Default")
      (node (ref "C10") (pin "1") (pinfunction "1_1") (pintype "passive"))
      (node (ref "R23") (pin "1") (pinfunction "1_1") (pintype "passive"))
      (node (ref "X9") (pin "3") (pinfunction "CT_3") (pintype "input"))
    )
    (net (code "52") (name "Net-(X9-RD+)") (class "Default")
      (node (ref "C15") (pin "2") (pinfunction "2_2") (pintype "passive"))
      (node (ref "X9") (pin "7") (pinfunction "RD+_7") (pintype "input"))
    )
    (net (code "53") (name "Net-(X9-RD-)") (class "Default")
      (node (ref "C21") (pin "2") (pinfunction "2_2") (pintype "passive"))
      (node (ref "X9") (pin "8") (pinfunction "RD-_8") (pintype "input"))
    )
    (net (code "54") (name "RG-11") (class "Default")
      (node (ref "U$3") (pin "P$13") (pinfunction "Y5_P$13") (pintype "output"))
      (node (ref "U2") (pin "9") (pinfunction "IO25_9") (pintype "bidirectional"))
    )
    (net (code "55") (name "RG-11-IN_5V") (class "Default")
      (node (ref "C1") (pin "1") (pinfunction "1_1") (pintype "passive"))
      (node (ref "R4") (pin "1") (pinfunction "1_1") (pintype "passive"))
      (node (ref "R5") (pin "1") (pinfunction "1_1") (pintype "passive"))
      (node (ref "U$3") (pin "P$7") (pinfunction "A5_P$7") (pintype "input"))
    )
    (net (code "56") (name "RG-11-IN_EXT") (class "Default")
      (node (ref "R5") (pin "2") (pinfunction "2_2") (pintype "passive"))
      (node (ref "X5") (pin "2") (pinfunction "KL_2") (pintype "passive"))
    )
    (net (code "57") (name "RX2") (class "Default")
      (node (ref "JP1") (pin "2") (pinfunction "2_2") (pintype "passive"))
      (node (ref "U2") (pin "27") (pinfunction "IO16_27") (pintype "bidirectional"))
    )
    (net (code "58") (name "RXD0") (class "Default")
      (node (ref "U2") (pin "34") (pinfunction "RXD0_34") (pintype "input"))
    )
    (net (code "59") (name "RXN") (class "Default")
      (node (ref "C21") (pin "1") (pinfunction "1_1") (pintype "passive"))
      (node (ref "R26") (pin "1") (pinfunction "1_1") (pintype "passive"))
      (node (ref "U1") (pin "5") (pinfunction "RXN_5") (pintype "passive"))
    )
    (net (code "60") (name "RXP") (class "Default")
      (node (ref "C15") (pin "1") (pinfunction "1_1") (pintype "passive"))
      (node (ref "R27") (pin "1") (pinfunction "1_1") (pintype "passive"))
      (node (ref "U1") (pin "6") (pinfunction "RXP_6") (pintype "passive"))
    )
    (net (code "61") (name "SCL") (class "Default")
      (node (ref "IC2") (pin "6") (pinfunction "SCL_6") (pintype "input"))
      (node (ref "R1") (pin "1") (pinfunction "1_1") (pintype "passive"))
      (node (ref "U2") (pin "36") (pinfunction "IO22_36") (pintype "bidirectional"))
    )
    (net (code "62") (name "SCLK") (class "Default")
      (node (ref "U1") (pin "33") (pinfunction "SCLK_33") (pintype "passive"))
      (node (ref "U2") (pin "30") (pinfunction "IO18_30") (pintype "bidirectional"))
    )
    (net (code "63") (name "SDA") (class "Default")
      (node (ref "IC2") (pin "5") (pinfunction "SDA_5") (pintype "bidirectional"))
      (node (ref "R3") (pin "1") (pinfunction "1_1") (pintype "passive"))
      (node (ref "U2") (pin "33") (pinfunction "IO21_33") (pintype "bidirectional"))
    )
    (net (code "64") (name "SDI") (class "Default")
      (node (ref "U1") (pin "34") (pinfunction "MISO_34") (pintype "passive"))
      (node (ref "U2") (pin "31") (pinfunction "IO19_31") (pintype "bidirectional"))
    )
    (net (code "65") (name "SDO") (class "Default")
      (node (ref "U1") (pin "35") (pinfunction "MOSI_35") (pintype "passive"))
      (node (ref "U2") (pin "37") (pinfunction "IO23_37") (pintype "bidirectional"))
    )
    (net (code "66") (name "SHUTTER_OPENED") (class "Default")
      (node (ref "U$3") (pin "P$12") (pinfunction "Y6_P$12") (pintype "output"))
      (node (ref "U2") (pin "8") (pinfunction "IO33_8") (pintype "bidirectional"))
    )
    (net (code "67") (name "SHUTTER_OPENED-IN_EXT") (class "Default")
      (node (ref "R48") (pin "2") (pinfunction "2_2") (pintype "passive"))
      (node (ref "X3") (pin "2") (pinfunction "KL_2") (pintype "passive"))
    )
    (net (code "68") (name "SHUTTER_OPENED_IN_5V") (class "Default")
      (node (ref "C44") (pin "1") (pinfunction "1_1") (pintype "passive"))
      (node (ref "R17") (pin "2") (pinfunction "2_2") (pintype "passive"))
      (node (ref "R48") (pin "1") (pinfunction "1_1") (pintype "passive"))
      (node (ref "U$3") (pin "P$8") (pinfunction "A6_P$8") (pintype "input"))
    )
    (net (code "69") (name "SPARE1") (class "Default")
      (node (ref "U$3") (pin "P$18") (pinfunction "Y0_P$18") (pintype "output"))
      (node (ref "U2") (pin "5") (pinfunction "IO34_5") (pintype "bidirectional"))
    )
    (net (code "70") (name "SPARE1-IN_EXT") (class "Default")
      (node (ref "R45") (pin "2") (pinfunction "2_2") (pintype "passive"))
      (node (ref "X8") (pin "1") (pinfunction "KL_1") (pintype "passive"))
    )
    (net (code "71") (name "SPARE1_IN_5V") (class "Default")
      (node (ref "C41") (pin "1") (pinfunction "1_1") (pintype "passive"))
      (node (ref "R21") (pin "2") (pinfunction "2_2") (pintype "passive"))
      (node (ref "R45") (pin "1") (pinfunction "1_1") (pintype "passive"))
      (node (ref "U$3") (pin "P$2") (pinfunction "A0_P$2") (pintype "input"))
    )
    (net (code "72") (name "SPARE2") (class "Default")
      (node (ref "U$3") (pin "P$14") (pinfunction "Y4_P$14") (pintype "output"))
      (node (ref "U2") (pin "10") (pinfunction "IO26_10") (pintype "bidirectional"))
    )
    (net (code "73") (name "SPARE2-IN_EXT") (class "Default")
      (node (ref "R49") (pin "2") (pinfunction "2_2") (pintype "passive"))
      (node (ref "X8") (pin "2") (pinfunction "KL_2") (pintype "passive"))
    )
    (net (code "74") (name "SPARE2_IN_5V") (class "Default")
      (node (ref "C45") (pin "1") (pinfunction "1_1") (pintype "passive"))
      (node (ref "R49") (pin "1") (pinfunction "1_1") (pintype "passive"))
      (node (ref "R9") (pin "2") (pinfunction "2_2") (pintype "passive"))
      (node (ref "U$3") (pin "P$6") (pinfunction "A4_P$6") (pintype "input"))
    )
    (net (code "75") (name "SPARE_OUT1") (class "Default")
      (node (ref "U$1") (pin "P$5") (pinfunction "A3_P$5") (pintype "input"))
      (node (ref "U2") (pin "25") (pinfunction "IO0_25") (pintype "bidirectional"))
    )
    (net (code "76") (name "SPARE_OUT1_5V") (class "Default")
      (node (ref "U$1") (pin "P$15") (pinfunction "Y3_P$15") (pintype "output"))
      (node (ref "X7") (pin "3") (pinfunction "KL_3") (pintype "passive"))
    )
    (net (code "77") (name "SPARE_OUT2") (class "Default")
      (node (ref "U$1") (pin "P$6") (pinfunction "A4_P$6") (pintype "input"))
      (node (ref "U2") (pin "13") (pinfunction "IO12_13") (pintype "bidirectional"))
    )
    (net (code "78") (name "SPARE_OUT2_5V") (class "Default")
      (node (ref "U$1") (pin "P$14") (pinfunction "Y4_P$14") (pintype "output"))
      (node (ref "X7") (pin "2") (pinfunction "KL_2") (pintype "passive"))
    )
    (net (code "79") (name "STEP_5V_OUT") (class "Default")
      (node (ref "T3") (pin "2") (pinfunction "E_2") (pintype "passive"))
      (node (ref "X6") (pin "2") (pinfunction "KL_2") (pintype "passive"))
    )
    (net (code "80") (name "TX2") (class "Default")
      (node (ref "JP1") (pin "1") (pinfunction "1_1") (pintype "passive"))
      (node (ref "U2") (pin "28") (pinfunction "IO17_28") (pintype "bidirectional"))
    )
    (net (code "81") (name "TXD0") (class "Default")
      (node (ref "U2") (pin "35") (pinfunction "TXD0_35") (pintype "output"))
    )
    (net (code "82") (name "TXN") (class "Default")
      (node (ref "R25") (pin "1") (pinfunction "1_1") (pintype "passive"))
      (node (ref "U1") (pin "1") (pinfunction "TXN_1") (pintype "passive"))
      (node (ref "X9") (pin "2") (pinfunction "TD-_2") (pintype "input"))
    )
    (net (code "83") (name "TXP") (class "Default")
      (node (ref "R24") (pin "1") (pinfunction "1_1") (pintype "passive"))
      (node (ref "U1") (pin "2") (pinfunction "TXP_2") (pintype "passive"))
      (node (ref "X9") (pin "1") (pinfunction "TD+_1") (pintype "input"))
    )
    (net (code "84") (name "VCC") (class "Default")
      (node (ref "C23") (pin "1") (pinfunction "1_1") (pintype "passive"))
      (node (ref "C28") (pin "1") (pinfunction "1_1") (pintype "passive"))
      (node (ref "C6") (pin "1") (pinfunction "1_1") (pintype "passive"))
      (node (ref "IC1") (pin "2") (pinfunction "VOUT_1_2") (pintype "bidirectional"))
      (node (ref "IC1") (pin "4") (pinfunction "VOUT_2_4") (pintype "bidirectional"))
      (node (ref "IC8") (pin "3") (pinfunction "VIN_3") (pintype "input"))
      (node (ref "R15") (pin "1") (pinfunction "1_1") (pintype "passive"))
      (node (ref "R16") (pin "1") (pinfunction "1_1") (pintype "passive"))
      (node (ref "R17") (pin "1") (pinfunction "1_1") (pintype "passive"))
      (node (ref "R18") (pin "1") (pinfunction "1_1") (pintype "passive"))
      (node (ref "R20") (pin "2") (pinfunction "2_2") (pintype "passive"))
      (node (ref "R21") (pin "1") (pinfunction "1_1") (pintype "passive"))
      (node (ref "R4") (pin "2") (pinfunction "2_2") (pintype "passive"))
      (node (ref "R9") (pin "1") (pinfunction "1_1") (pintype "passive"))
      (node (ref "T1") (pin "3") (pinfunction "C_3") (pintype "passive"))
      (node (ref "T2") (pin "3") (pinfunction "C_3") (pintype "passive"))
      (node (ref "T3") (pin "3") (pinfunction "C_3") (pintype "passive"))
      (node (ref "U$1") (pin "P$20") (pinfunction "VCC_P$20") (pintype "power_in"))
      (node (ref "U2") (pin "19") (pinfunction "EXT_5V_19") (pintype "power_in"))
      (node (ref "X10") (pin "3") (pinfunction "KL_3") (pintype "passive"))
      (node (ref "X2") (pin "3") (pinfunction "KL_3") (pintype "passive"))
      (node (ref "X6") (pin "3") (pinfunction "KL_3") (pintype "passive"))
    )
    (net (code "85") (name "VPIN") (class "Default")
      (node (ref "R2") (pin "1") (pinfunction "1_1") (pintype "passive"))
      (node (ref "R6") (pin "2") (pinfunction "2_2") (pintype "passive"))
      (node (ref "U2") (pin "3") (pinfunction "SENSOR_VP_3") (pintype "input"))
    )
    (net (code "86") (name "XI") (class "Default")
      (node (ref "25MHZ") (pin "3") (pinfunction "FO_3") (pintype "output"))
      (node (ref "U1") (pin "30") (pinfunction "XI/CLKIN_30") (pintype "passive"))
    )
    (net (code "87") (name "XO") (class "Default")
      (node (ref "U1") (pin "31") (pinfunction "XO_31") (pintype "passive"))
    )
    (net (code "88") (name "unconnected-(IC2-WP-Pad7)") (class "Default")
      (node (ref "IC2") (pin "7") (pinfunction "WP_7") (pintype "input"))
    )
    (net (code "89") (name "unconnected-(J2-Pad3)") (class "Default")
      (node (ref "J2") (pin "3") (pinfunction "3_3") (pintype "bidirectional"))
    )
    (net (code "90") (name "unconnected-(J2-Pad4)") (class "Default")
      (node (ref "J2") (pin "4") (pinfunction "4_4") (pintype "bidirectional"))
    )
    (net (code "91") (name "unconnected-(U$1A-Y5-PadP$13)") (class "Default")
      (node (ref "U$1") (pin "P$13") (pinfunction "Y5_P$13") (pintype "output"))
    )
    (net (code "92") (name "unconnected-(U$1A-Y6-PadP$12)") (class "Default")
      (node (ref "U$1") (pin "P$12") (pinfunction "Y6_P$12") (pintype "output"))
    )
    (net (code "93") (name "unconnected-(U$1A-Y7-PadP$11)") (class "Default")
      (node (ref "U$1") (pin "P$11") (pinfunction "Y7_P$11") (pintype "output"))
    )
    (net (code "94") (name "unconnected-(U1-DNC-Pad7)") (class "Default")
      (node (ref "U1") (pin "7") (pinfunction "DNC_7") (pintype "passive"))
    )
    (net (code "95") (name "unconnected-(U1-DUPLED-Pad26)") (class "Default")
      (node (ref "U1") (pin "26") (pinfunction "DUPLED_26") (pintype "passive"))
    )
    (net (code "96") (name "unconnected-(U1-NC-Pad12)") (class "Default")
      (node (ref "U1") (pin "12") (pinfunction "NC_12") (pintype "passive"))
    )
    (net (code "97") (name "unconnected-(U1-NC-Pad13)") (class "Default")
      (node (ref "U1") (pin "13") (pinfunction "NC_13") (pintype "passive"))
    )
    (net (code "98") (name "unconnected-(U1-NC-Pad46)") (class "Default")
      (node (ref "U1") (pin "46") (pinfunction "NC_46") (pintype "passive"))
    )
    (net (code "99") (name "unconnected-(U1-NC-Pad47)") (class "Default")
      (node (ref "U1") (pin "47") (pinfunction "NC_47") (pintype "passive"))
    )
    (net (code "100") (name "unconnected-(U1-SPDLED-Pad24)") (class "Default")
      (node (ref "U1") (pin "24") (pinfunction "SPDLED_24") (pintype "passive"))
    )
    (net (code "101") (name "unconnected-(U1-VBG-Pad18)") (class "Default")
      (node (ref "U1") (pin "18") (pinfunction "VBG_18") (pintype "passive"))
    )
    (net (code "102") (name "unconnected-(U2-3V3-Pad1)") (class "Default")
      (node (ref "U2") (pin "1") (pinfunction "3V3_1") (pintype "power_in"))
    )
    (net (code "103") (name "unconnected-(U2-CLK-Pad20)") (class "Default")
      (node (ref "U2") (pin "20") (pinfunction "CLK_20") (pintype "input"))
    )
    (net (code "104") (name "unconnected-(U2-CMD-Pad18)") (class "Default")
      (node (ref "U2") (pin "18") (pinfunction "CMD_18") (pintype "bidirectional"))
    )
    (net (code "105") (name "unconnected-(U2-EN-Pad2)") (class "Default")
      (node (ref "U2") (pin "2") (pinfunction "EN_2") (pintype "input"))
    )
    (net (code "106") (name "unconnected-(U2-SD0-Pad21)") (class "Default")
      (node (ref "U2") (pin "21") (pinfunction "SD0_21") (pintype "bidirectional"))
    )
    (net (code "107") (name "unconnected-(U2-SD1-Pad22)") (class "Default")
      (node (ref "U2") (pin "22") (pinfunction "SD1_22") (pintype "bidirectional"))
    )
    (net (code "108") (name "unconnected-(U2-SD2-Pad16)") (class "Default")
      (node (ref "U2") (pin "16") (pinfunction "SD2_16") (pintype "bidirectional"))
    )
    (net (code "109") (name "unconnected-(U2-SD3-Pad17)") (class "Default")
      (node (ref "U2") (pin "17") (pinfunction "SD3_17") (pintype "bidirectional"))
    )
    (net (code "110") (name "unconnected-(U2-SENSOR_VN-Pad4)") (class "Default")
      (node (ref "U2") (pin "4") (pinfunction "SENSOR_VN_4") (pintype "input"))
    )
  )
)
